# housesensor.net
KiCad netlist of a schematic drawn in EAGLE
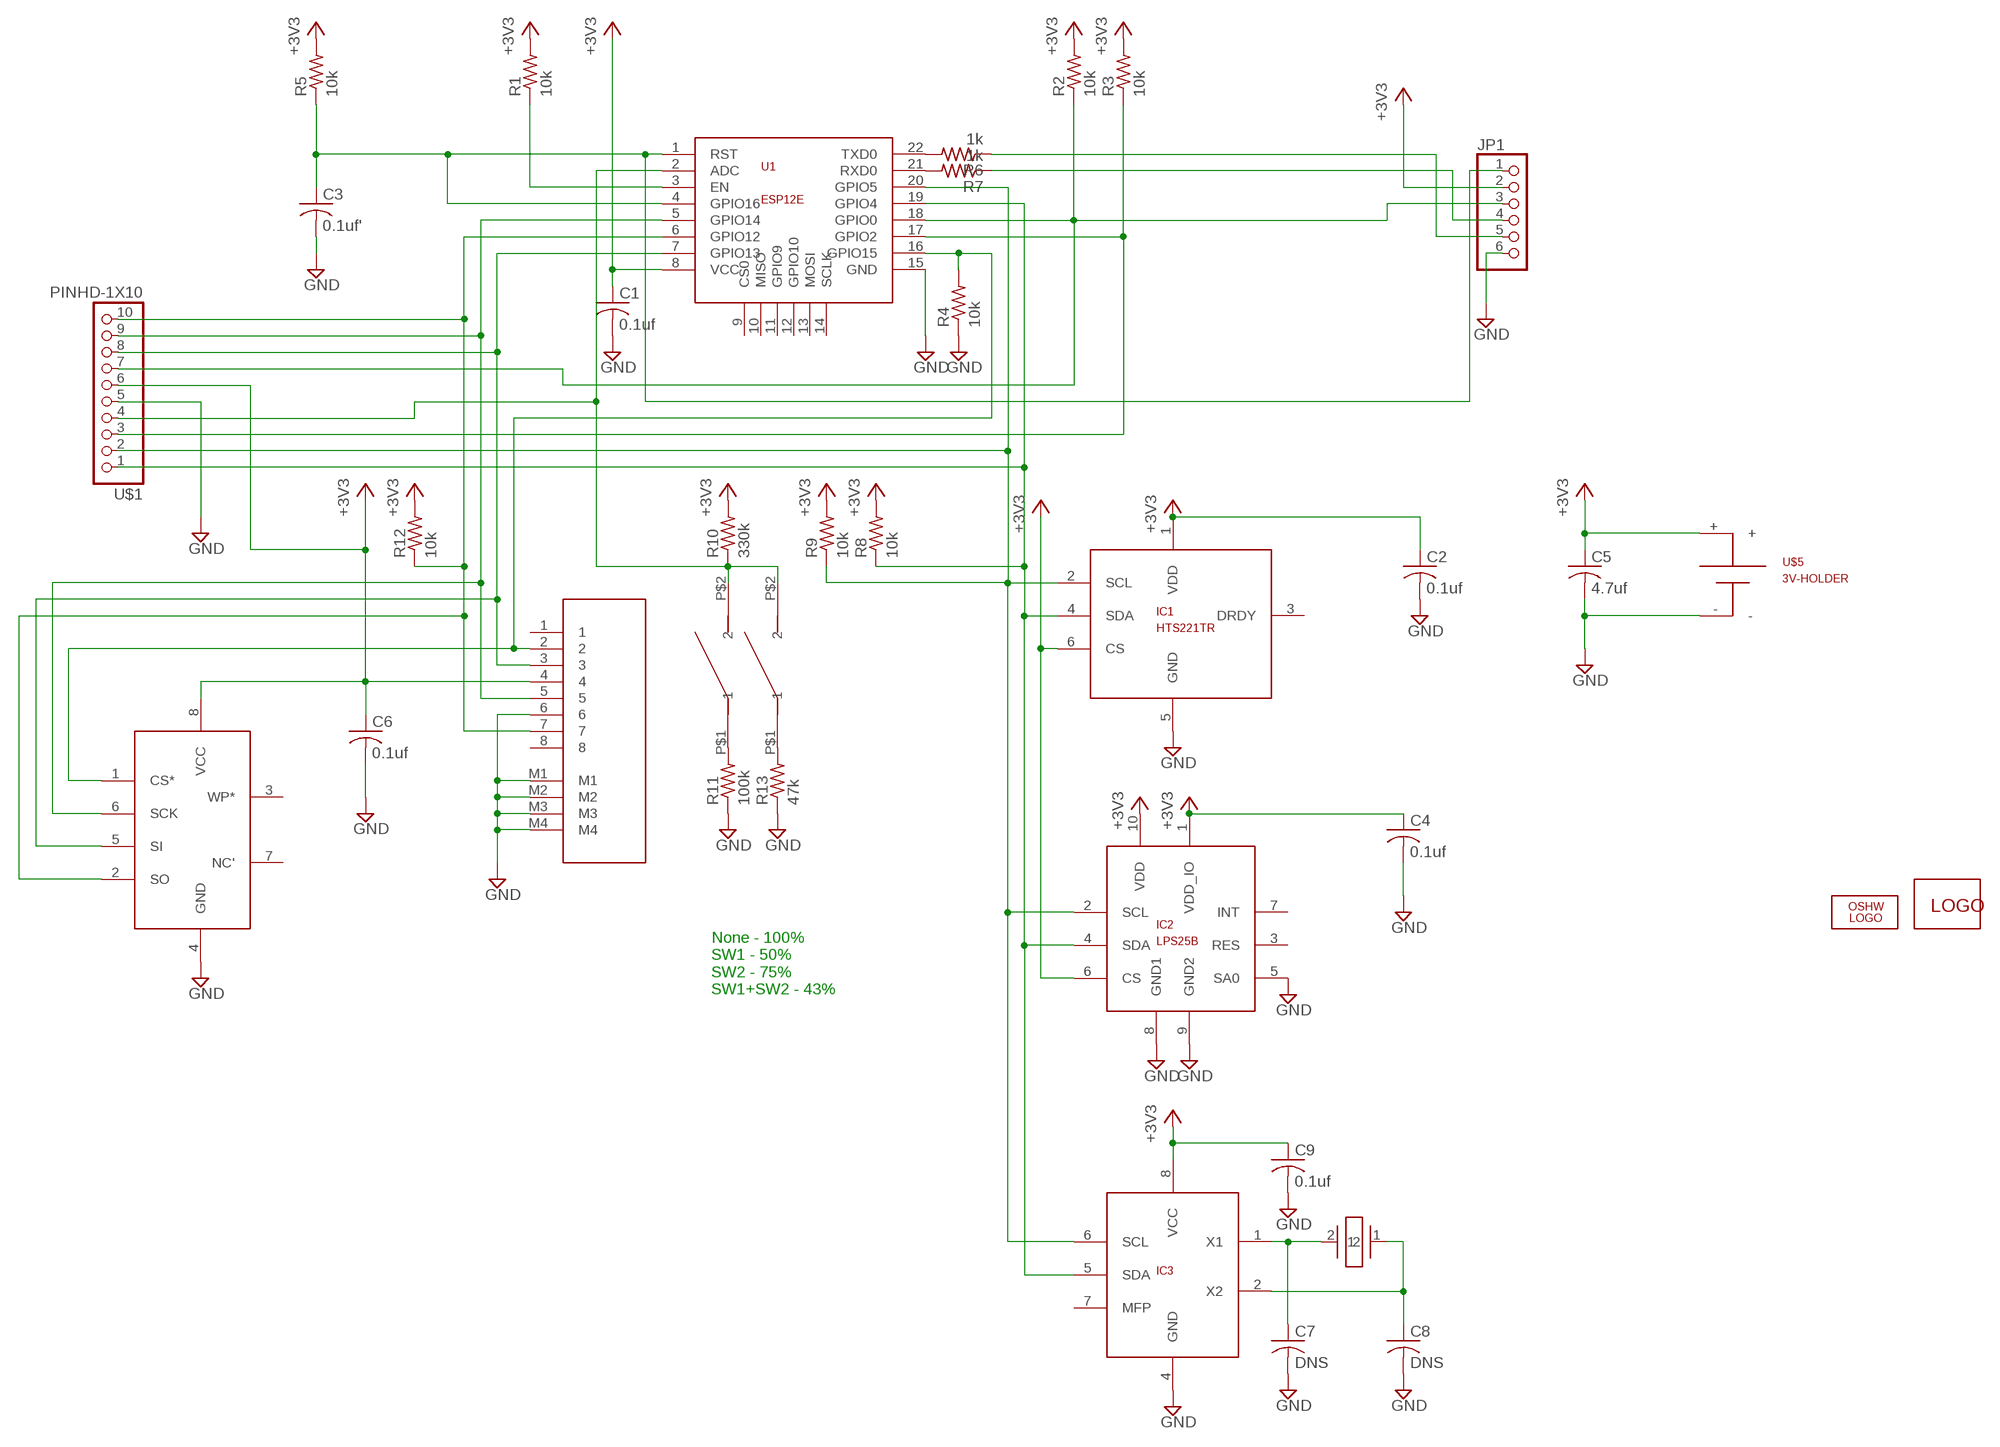
[diagram p0: schematic, sheet 1]

(export (version "E")
  (design (tool "Eeschema 10.0.6"))
  (components
    (comp (ref "C1")
      (value "0.1uf")
      (footprint "eagle-import:C0603")
      (libsource (lib "eagle-import") (part "C-USC0603"))
    )
    (comp (ref "C2")
      (value "0.1uf")
      (footprint "eagle-import:C0603")
      (libsource (lib "eagle-import") (part "C-USC0603"))
    )
    (comp (ref "C3")
      (value "0.1uf'")
      (footprint "eagle-import:C0603")
      (libsource (lib "eagle-import") (part "C-USC0603"))
    )
    (comp (ref "C4")
      (value "0.1uf")
      (footprint "eagle-import:C0603")
      (libsource (lib "eagle-import") (part "C-USC0603"))
    )
    (comp (ref "C5")
      (value "4.7uf")
      (footprint "eagle-import:C1206")
      (libsource (lib "eagle-import") (part "C-USC1206"))
    )
    (comp (ref "C6")
      (value "0.1uf")
      (footprint "eagle-import:C0603")
      (libsource (lib "eagle-import") (part "C-USC0603"))
    )
    (comp (ref "C7")
      (value "DNS")
      (footprint "eagle-import:C0603")
      (libsource (lib "eagle-import") (part "C-USC0603"))
    )
    (comp (ref "C8")
      (value "DNS")
      (footprint "eagle-import:C0603")
      (libsource (lib "eagle-import") (part "C-USC0603"))
    )
    (comp (ref "C9")
      (value "0.1uf")
      (footprint "eagle-import:C0603")
      (libsource (lib "eagle-import") (part "C-USC0603"))
    )
    (comp (ref "IC1")
      (value "HTS221TR")
      (footprint "eagle-import:HTS221")
      (libsource (lib "eagle-import") (part "HTS221TR"))
    )
    (comp (ref "IC2")
      (value "LPS25B")
      (footprint "eagle-import:LPS25")
      (libsource (lib "eagle-import") (part "LPS25B"))
    )
    (comp (ref "IC3")
      (value "MCP7940MS08M")
      (footprint "eagle-import:SO8M")
      (libsource (lib "eagle-import") (part "MCP7940MS08M"))
    )
    (comp (ref "IC4")
      (value "SPI-FLASH")
      (footprint "eagle-import:SO8J")
      (libsource (lib "eagle-import") (part "SPI-FLASH"))
    )
    (comp (ref "JP1")
      (value "PINHD-1X6")
      (footprint "eagle-import:1X06")
      (libsource (lib "eagle-import") (part "PINHD-1X6"))
    )
    (comp (ref "LOGO1")
      (value "OSHW_LOGO_FILLX0150-NT")
      (footprint "eagle-import:OSHW_FILLX150_NOTEXT")
      (libsource (lib "eagle-import") (part "OSHW_LOGO_FILLX0150-NT"))
    )
    (comp (ref "R1")
      (value "10k")
      (footprint "eagle-import:R0603")
      (libsource (lib "eagle-import") (part "R-US_R0603"))
    )
    (comp (ref "R2")
      (value "10k")
      (footprint "eagle-import:R0603")
      (libsource (lib "eagle-import") (part "R-US_R0603"))
    )
    (comp (ref "R3")
      (value "10k")
      (footprint "eagle-import:R0603")
      (libsource (lib "eagle-import") (part "R-US_R0603"))
    )
    (comp (ref "R4")
      (value "10k")
      (footprint "eagle-import:R0603")
      (libsource (lib "eagle-import") (part "R-US_R0603"))
    )
    (comp (ref "R5")
      (value "10k")
      (footprint "eagle-import:R0603")
      (libsource (lib "eagle-import") (part "R-US_R0603"))
    )
    (comp (ref "R6")
      (value "1k")
      (footprint "eagle-import:R0603")
      (libsource (lib "eagle-import") (part "R-US_R0603"))
    )
    (comp (ref "R7")
      (value "1k")
      (footprint "eagle-import:R0603")
      (libsource (lib "eagle-import") (part "R-US_R0603"))
    )
    (comp (ref "R8")
      (value "10k")
      (footprint "eagle-import:R0603")
      (libsource (lib "eagle-import") (part "R-US_R0603"))
    )
    (comp (ref "R9")
      (value "10k")
      (footprint "eagle-import:R0603")
      (libsource (lib "eagle-import") (part "R-US_R0603"))
    )
    (comp (ref "R10")
      (value "330k")
      (footprint "eagle-import:R0603")
      (libsource (lib "eagle-import") (part "R-US_R0603"))
    )
    (comp (ref "R11")
      (value "100k")
      (footprint "eagle-import:R0603")
      (libsource (lib "eagle-import") (part "R-US_R0603"))
    )
    (comp (ref "R12")
      (value "10k")
      (footprint "eagle-import:R0603")
      (libsource (lib "eagle-import") (part "R-US_R0603"))
    )
    (comp (ref "R13")
      (value "47k")
      (footprint "eagle-import:R0603")
      (libsource (lib "eagle-import") (part "R-US_R0603"))
    )
    (comp (ref "SW1")
      (value "RED-SWITCH")
      (footprint "eagle-import:SW2")
      (libsource (lib "eagle-import") (part "RED-SWITCH"))
    )
    (comp (ref "SW2")
      (value "RED-SWITCH")
      (footprint "eagle-import:SW2")
      (libsource (lib "eagle-import") (part "RED-SWITCH"))
    )
    (comp (ref "U$1")
      (value "PINHD-1X10")
      (footprint "eagle-import:1X10-BIG")
      (libsource (lib "eagle-import") (part "PINHD-1X10"))
    )
    (comp (ref "U$4")
      (value "MICRO-SD-SCHD1A0101")
      (footprint "eagle-import:MICROSD-P")
      (libsource (lib "eagle-import") (part "MICRO-SD-SCHD1A0101"))
    )
    (comp (ref "U$5")
      (value "3V-HOLDER")
      (footprint "eagle-import:3V-HOLDER")
      (libsource (lib "eagle-import") (part "3V-HOLDER"))
    )
    (comp (ref "U$6")
      (value "MOONBASE-LOGO")
      (footprint "eagle-import:MOONBASE-LOGO")
      (libsource (lib "eagle-import") (part "MOONBASE-LOGO"))
    )
    (comp (ref "U1")
      (value "ESP12E")
      (footprint "eagle-import:ESP8266-SMD")
      (libsource (lib "eagle-import") (part "ESP12E"))
    )
    (comp (ref "X1")
      (value "32KHZ")
      (footprint "eagle-import:32KHZ")
      (libsource (lib "eagle-import") (part "32KHZ"))
    )
  )
  (nets
    (net (code "1") (name "+3V3") (class "Default")
      (node (ref "C1") (pin "1") (pinfunction "1_1") (pintype "passive"))
      (node (ref "C2") (pin "1") (pinfunction "1_1") (pintype "passive"))
      (node (ref "C4") (pin "1") (pinfunction "1_1") (pintype "passive"))
      (node (ref "C5") (pin "1") (pinfunction "1_1") (pintype "passive"))
      (node (ref "C6") (pin "1") (pinfunction "1_1") (pintype "passive"))
      (node (ref "C9") (pin "1") (pinfunction "1_1") (pintype "passive"))
      (node (ref "IC1") (pin "1") (pinfunction "VDD_1") (pintype "bidirectional"))
      (node (ref "IC1") (pin "6") (pinfunction "CS_6") (pintype "bidirectional"))
      (node (ref "IC2") (pin "1") (pinfunction "VDD_IO_1") (pintype "bidirectional"))
      (node (ref "IC2") (pin "10") (pinfunction "VDD_10") (pintype "bidirectional"))
      (node (ref "IC2") (pin "6") (pinfunction "CS_6") (pintype "bidirectional"))
      (node (ref "IC3") (pin "8") (pinfunction "VCC_8") (pintype "bidirectional"))
      (node (ref "IC4") (pin "8") (pinfunction "VCC_8") (pintype "bidirectional"))
      (node (ref "JP1") (pin "2") (pinfunction "2_2") (pintype "passive"))
      (node (ref "R1") (pin "2") (pinfunction "2_2") (pintype "passive"))
      (node (ref "R10") (pin "2") (pinfunction "2_2") (pintype "passive"))
      (node (ref "R12") (pin "2") (pinfunction "2_2") (pintype "passive"))
      (node (ref "R2") (pin "2") (pinfunction "2_2") (pintype "passive"))
      (node (ref "R3") (pin "2") (pinfunction "2_2") (pintype "passive"))
      (node (ref "R5") (pin "2") (pinfunction "2_2") (pintype "passive"))
      (node (ref "R8") (pin "2") (pinfunction "2_2") (pintype "passive"))
      (node (ref "R9") (pin "2") (pinfunction "2_2") (pintype "passive"))
      (node (ref "U$1") (pin "6") (pinfunction "6_6") (pintype "passive"))
      (node (ref "U$4") (pin "4") (pinfunction "4_4") (pintype "bidirectional"))
      (node (ref "U$5") (pin "+") (pinfunction "+_+") (pintype "bidirectional"))
      (node (ref "U1") (pin "8") (pinfunction "VCC_8") (pintype "bidirectional"))
    )
    (net (code "2") (name "GND") (class "Default")
      (node (ref "C1") (pin "2") (pinfunction "2_2") (pintype "passive"))
      (node (ref "C2") (pin "2") (pinfunction "2_2") (pintype "passive"))
      (node (ref "C3") (pin "2") (pinfunction "2_2") (pintype "passive"))
      (node (ref "C4") (pin "2") (pinfunction "2_2") (pintype "passive"))
      (node (ref "C5") (pin "2") (pinfunction "2_2") (pintype "passive"))
      (node (ref "C6") (pin "2") (pinfunction "2_2") (pintype "passive"))
      (node (ref "C7") (pin "2") (pinfunction "2_2") (pintype "passive"))
      (node (ref "C8") (pin "2") (pinfunction "2_2") (pintype "passive"))
      (node (ref "C9") (pin "2") (pinfunction "2_2") (pintype "passive"))
      (node (ref "IC1") (pin "5") (pinfunction "GND_5") (pintype "bidirectional"))
      (node (ref "IC2") (pin "5") (pinfunction "SA0_5") (pintype "bidirectional"))
      (node (ref "IC2") (pin "8") (pinfunction "GND1_8") (pintype "bidirectional"))
      (node (ref "IC2") (pin "9") (pinfunction "GND2_9") (pintype "bidirectional"))
      (node (ref "IC3") (pin "4") (pinfunction "GND_4") (pintype "bidirectional"))
      (node (ref "IC4") (pin "4") (pinfunction "GND_4") (pintype "bidirectional"))
      (node (ref "JP1") (pin "6") (pinfunction "6_6") (pintype "passive"))
      (node (ref "R11") (pin "1") (pinfunction "1_1") (pintype "passive"))
      (node (ref "R13") (pin "1") (pinfunction "1_1") (pintype "passive"))
      (node (ref "R4") (pin "1") (pinfunction "1_1") (pintype "passive"))
      (node (ref "U$1") (pin "5") (pinfunction "5_5") (pintype "passive"))
      (node (ref "U$4") (pin "6") (pinfunction "6_6") (pintype "bidirectional"))
      (node (ref "U$4") (pin "M1") (pinfunction "M1_M1") (pintype "bidirectional"))
      (node (ref "U$4") (pin "M2") (pinfunction "M2_M2") (pintype "bidirectional"))
      (node (ref "U$4") (pin "M3") (pinfunction "M3_M3") (pintype "bidirectional"))
      (node (ref "U$4") (pin "M4") (pinfunction "M4_M4") (pintype "bidirectional"))
      (node (ref "U$5") (pin "-") (pinfunction "-_-") (pintype "bidirectional"))
      (node (ref "U1") (pin "15") (pinfunction "GND_15") (pintype "bidirectional"))
    )
    (net (code "3") (name "Net-(IC1-SCL)") (class "Default")
      (node (ref "IC1") (pin "2") (pinfunction "SCL_2") (pintype "bidirectional"))
      (node (ref "IC2") (pin "2") (pinfunction "SCL_2") (pintype "bidirectional"))
      (node (ref "IC3") (pin "6") (pinfunction "SCL_6") (pintype "bidirectional"))
      (node (ref "R9") (pin "1") (pinfunction "1_1") (pintype "passive"))
      (node (ref "U$1") (pin "2") (pinfunction "2_2") (pintype "passive"))
      (node (ref "U1") (pin "20") (pinfunction "GPIO5_20") (pintype "bidirectional"))
    )
    (net (code "4") (name "Net-(IC1-SDA)") (class "Default")
      (node (ref "IC1") (pin "4") (pinfunction "SDA_4") (pintype "bidirectional"))
      (node (ref "IC2") (pin "4") (pinfunction "SDA_4") (pintype "bidirectional"))
      (node (ref "IC3") (pin "5") (pinfunction "SDA_5") (pintype "bidirectional"))
      (node (ref "R8") (pin "1") (pinfunction "1_1") (pintype "passive"))
      (node (ref "U$1") (pin "1") (pinfunction "1_1") (pintype "passive"))
      (node (ref "U1") (pin "19") (pinfunction "GPIO4_19") (pintype "bidirectional"))
    )
    (net (code "5") (name "Net-(IC3-X1)") (class "Default")
      (node (ref "C7") (pin "1") (pinfunction "1_1") (pintype "passive"))
      (node (ref "IC3") (pin "1") (pinfunction "X1_1") (pintype "bidirectional"))
      (node (ref "X1") (pin "2") (pinfunction "2_2") (pintype "bidirectional"))
    )
    (net (code "6") (name "Net-(IC3-X2)") (class "Default")
      (node (ref "C8") (pin "1") (pinfunction "1_1") (pintype "passive"))
      (node (ref "IC3") (pin "2") (pinfunction "X2_2") (pintype "bidirectional"))
      (node (ref "X1") (pin "1") (pinfunction "1_1") (pintype "bidirectional"))
    )
    (net (code "7") (name "Net-(IC4-CS*)") (class "Default")
      (node (ref "IC4") (pin "1") (pinfunction "CS*_1") (pintype "bidirectional"))
      (node (ref "R4") (pin "2") (pinfunction "2_2") (pintype "passive"))
      (node (ref "U$4") (pin "2") (pinfunction "2_2") (pintype "bidirectional"))
      (node (ref "U1") (pin "16") (pinfunction "GPIO15_16") (pintype "bidirectional"))
    )
    (net (code "8") (name "Net-(IC4-SCK)") (class "Default")
      (node (ref "IC4") (pin "6") (pinfunction "SCK_6") (pintype "bidirectional"))
      (node (ref "U$1") (pin "9") (pinfunction "9_9") (pintype "passive"))
      (node (ref "U$4") (pin "5") (pinfunction "5_5") (pintype "bidirectional"))
      (node (ref "U1") (pin "5") (pinfunction "GPIO14_5") (pintype "bidirectional"))
    )
    (net (code "9") (name "Net-(IC4-SI)") (class "Default")
      (node (ref "IC4") (pin "5") (pinfunction "SI_5") (pintype "bidirectional"))
      (node (ref "U$1") (pin "8") (pinfunction "8_8") (pintype "passive"))
      (node (ref "U$4") (pin "3") (pinfunction "3_3") (pintype "bidirectional"))
      (node (ref "U1") (pin "7") (pinfunction "GPIO13_7") (pintype "bidirectional"))
    )
    (net (code "10") (name "Net-(IC4-SO)") (class "Default")
      (node (ref "IC4") (pin "2") (pinfunction "SO_2") (pintype "bidirectional"))
      (node (ref "R12") (pin "1") (pinfunction "1_1") (pintype "passive"))
      (node (ref "U$1") (pin "10") (pinfunction "10_10") (pintype "passive"))
      (node (ref "U$4") (pin "7") (pinfunction "7_7") (pintype "bidirectional"))
      (node (ref "U1") (pin "6") (pinfunction "GPIO12_6") (pintype "bidirectional"))
    )
    (net (code "11") (name "Net-(JP1-Pad4)") (class "Default")
      (node (ref "JP1") (pin "4") (pinfunction "4_4") (pintype "passive"))
      (node (ref "R7") (pin "1") (pinfunction "1_1") (pintype "passive"))
    )
    (net (code "12") (name "Net-(JP1-Pad5)") (class "Default")
      (node (ref "JP1") (pin "5") (pinfunction "5_5") (pintype "passive"))
      (node (ref "R6") (pin "1") (pinfunction "1_1") (pintype "passive"))
    )
    (net (code "13") (name "Net-(SW1-1)") (class "Default")
      (node (ref "R11") (pin "2") (pinfunction "2_2") (pintype "passive"))
      (node (ref "SW1") (pin "P$1") (pinfunction "1_P$1") (pintype "bidirectional"))
    )
    (net (code "14") (name "Net-(SW1-2)") (class "Default")
      (node (ref "R10") (pin "1") (pinfunction "1_1") (pintype "passive"))
      (node (ref "SW1") (pin "P$2") (pinfunction "2_P$2") (pintype "bidirectional"))
      (node (ref "SW2") (pin "P$2") (pinfunction "2_P$2") (pintype "bidirectional"))
      (node (ref "U$1") (pin "4") (pinfunction "4_4") (pintype "passive"))
      (node (ref "U1") (pin "2") (pinfunction "ADC_2") (pintype "bidirectional"))
    )
    (net (code "15") (name "Net-(SW2-1)") (class "Default")
      (node (ref "R13") (pin "2") (pinfunction "2_2") (pintype "passive"))
      (node (ref "SW2") (pin "P$1") (pinfunction "1_P$1") (pintype "bidirectional"))
    )
    (net (code "16") (name "Net-(U1-EN)") (class "Default")
      (node (ref "R1") (pin "1") (pinfunction "1_1") (pintype "passive"))
      (node (ref "U1") (pin "3") (pinfunction "EN_3") (pintype "bidirectional"))
    )
    (net (code "17") (name "Net-(U1-GPIO0)") (class "Default")
      (node (ref "JP1") (pin "3") (pinfunction "3_3") (pintype "passive"))
      (node (ref "R2") (pin "1") (pinfunction "1_1") (pintype "passive"))
      (node (ref "U$1") (pin "7") (pinfunction "7_7") (pintype "passive"))
      (node (ref "U1") (pin "18") (pinfunction "GPIO0_18") (pintype "bidirectional"))
    )
    (net (code "18") (name "Net-(U1-GPIO2)") (class "Default")
      (node (ref "R3") (pin "1") (pinfunction "1_1") (pintype "passive"))
      (node (ref "U$1") (pin "3") (pinfunction "3_3") (pintype "passive"))
      (node (ref "U1") (pin "17") (pinfunction "GPIO2_17") (pintype "bidirectional"))
    )
    (net (code "19") (name "Net-(U1-GPIO16)") (class "Default")
      (node (ref "C3") (pin "1") (pinfunction "1_1") (pintype "passive"))
      (node (ref "JP1") (pin "1") (pinfunction "1_1") (pintype "passive"))
      (node (ref "R5") (pin "1") (pinfunction "1_1") (pintype "passive"))
      (node (ref "U1") (pin "1") (pinfunction "RST_1") (pintype "bidirectional"))
      (node (ref "U1") (pin "4") (pinfunction "GPIO16_4") (pintype "bidirectional"))
    )
    (net (code "20") (name "Net-(U1-RXD0)") (class "Default")
      (node (ref "R7") (pin "2") (pinfunction "2_2") (pintype "passive"))
      (node (ref "U1") (pin "21") (pinfunction "RXD0_21") (pintype "bidirectional"))
    )
    (net (code "21") (name "Net-(U1-TXD0)") (class "Default")
      (node (ref "R6") (pin "2") (pinfunction "2_2") (pintype "passive"))
      (node (ref "U1") (pin "22") (pinfunction "TXD0_22") (pintype "bidirectional"))
    )
    (net (code "22") (name "unconnected-(IC1-DRDY-Pad3)") (class "Default")
      (node (ref "IC1") (pin "3") (pinfunction "DRDY_3") (pintype "bidirectional"))
    )
    (net (code "23") (name "unconnected-(IC2-INT-Pad7)") (class "Default")
      (node (ref "IC2") (pin "7") (pinfunction "INT_7") (pintype "bidirectional"))
    )
    (net (code "24") (name "unconnected-(IC2-RES-Pad3)") (class "Default")
      (node (ref "IC2") (pin "3") (pinfunction "RES_3") (pintype "bidirectional"))
    )
    (net (code "25") (name "unconnected-(IC3-MFP-Pad7)") (class "Default")
      (node (ref "IC3") (pin "7") (pinfunction "MFP_7") (pintype "bidirectional"))
    )
    (net (code "26") (name "unconnected-(IC4-NC'-Pad7)") (class "Default")
      (node (ref "IC4") (pin "7") (pinfunction "NC'_7") (pintype "bidirectional"))
    )
    (net (code "27") (name "unconnected-(IC4-WP*-Pad3)") (class "Default")
      (node (ref "IC4") (pin "3") (pinfunction "WP*_3") (pintype "bidirectional"))
    )
    (net (code "28") (name "unconnected-(U$4-Pad1)") (class "Default")
      (node (ref "U$4") (pin "1") (pinfunction "1_1") (pintype "bidirectional"))
    )
    (net (code "29") (name "unconnected-(U$4-Pad8)") (class "Default")
      (node (ref "U$4") (pin "8") (pinfunction "8_8") (pintype "bidirectional"))
    )
    (net (code "30") (name "unconnected-(U1-CS0-Pad9)") (class "Default")
      (node (ref "U1") (pin "9") (pinfunction "CS0_9") (pintype "bidirectional"))
    )
    (net (code "31") (name "unconnected-(U1-GPIO9-Pad11)") (class "Default")
      (node (ref "U1") (pin "11") (pinfunction "GPIO9_11") (pintype "bidirectional"))
    )
    (net (code "32") (name "unconnected-(U1-GPIO10-Pad12)") (class "Default")
      (node (ref "U1") (pin "12") (pinfunction "GPIO10_12") (pintype "bidirectional"))
    )
    (net (code "33") (name "unconnected-(U1-MISO-Pad10)") (class "Default")
      (node (ref "U1") (pin "10") (pinfunction "MISO_10") (pintype "bidirectional"))
    )
    (net (code "34") (name "unconnected-(U1-MOSI-Pad13)") (class "Default")
      (node (ref "U1") (pin "13") (pinfunction "MOSI_13") (pintype "bidirectional"))
    )
    (net (code "35") (name "unconnected-(U1-SCLK-Pad14)") (class "Default")
      (node (ref "U1") (pin "14") (pinfunction "SCLK_14") (pintype "bidirectional"))
    )
  )
)
